# 4d_-_BSPD_Detection_Timer.net
KiCad netlist of a schematic drawn in Altium Designer
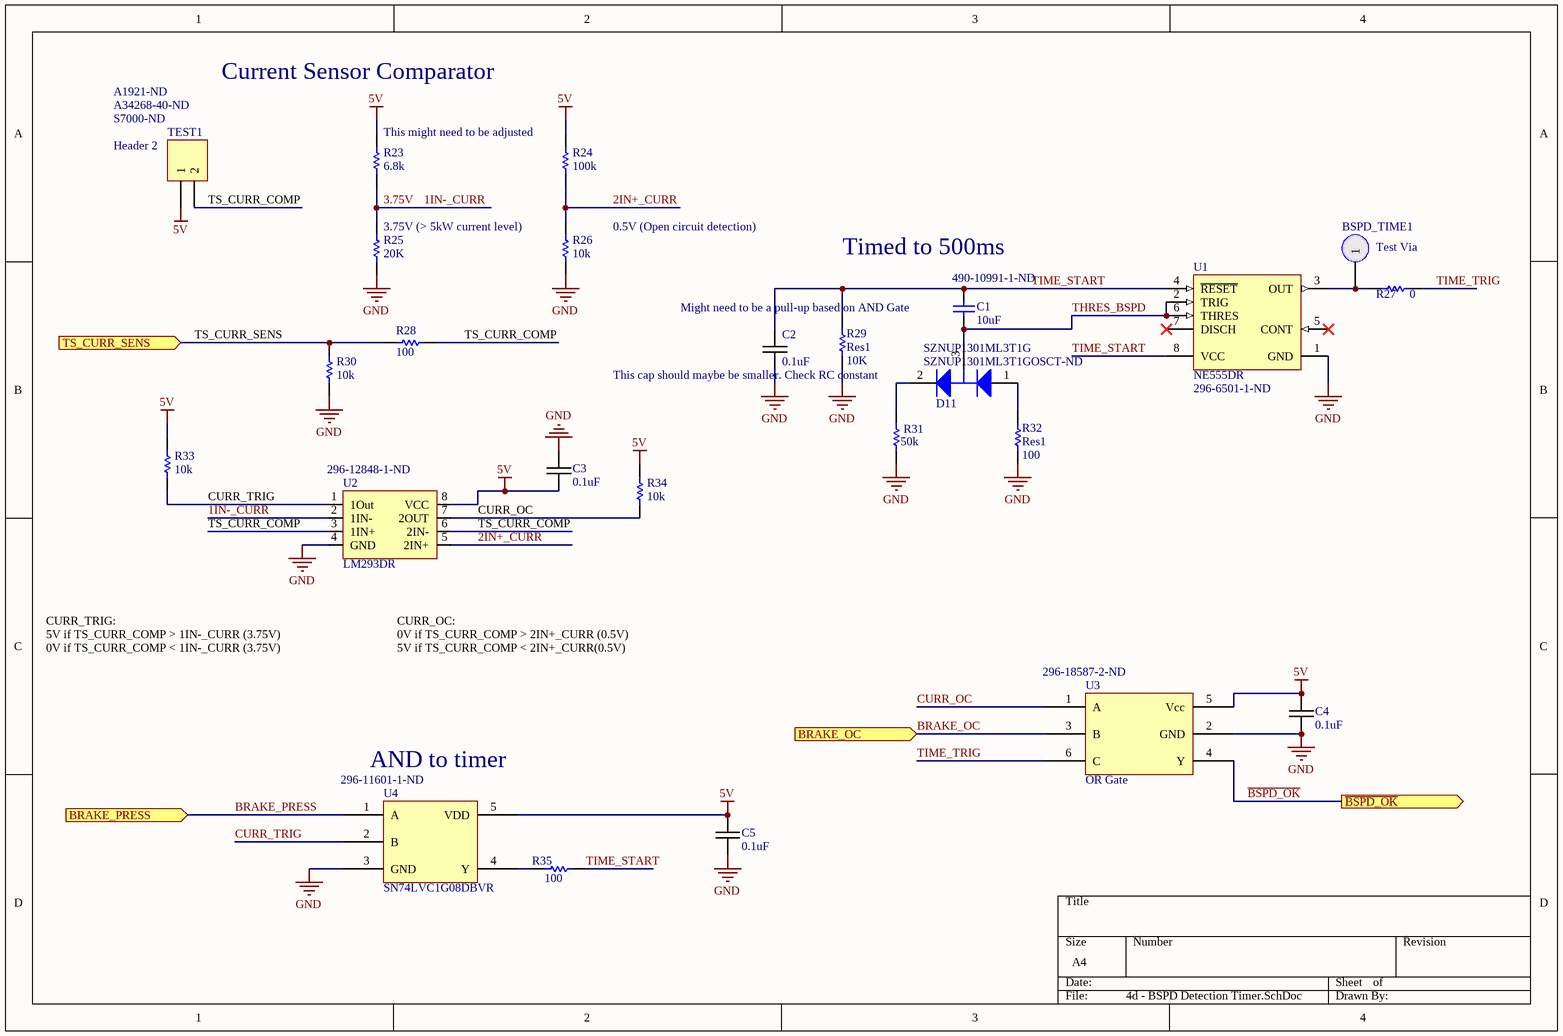
[diagram p0: 4d - BSPD Detection Timer.SchDoc]

(export (version "E")
  (design (tool "Eeschema 10.0.6"))
  (components
    (comp (ref "BSPD_TIME1")
      (value "Test Via")
      (footprint "Test Via")
      (libsource (lib "BRAKETEMPComponents") (part "Test VIa"))
    )
    (comp (ref "C1")
      (value "10uF")
      (footprint "1608[0603]")
      (description "Capacitor (Semiconductor SIM Model)")
      (fields
        (field (name "SUPPLIER PART NUMBER 1") "490-10991-1-ND")
        (field (name "Comment") "Cap Semi")
        (field (name "PUBLISHER") "Altium Limited")
      )
      (libsource (lib "Miscellaneous Devices") (part "Cap Semi"))
    )
    (comp (ref "C2")
      (value "0.1uF")
      (footprint "1608[0603]")
      (description "CAP CER 0.1UF 50V X7R 0603")
      (fields
        (field (name "MANUFACTURER") "Kemet")
        (field (name "MANUFACTURER PART NUMBER") "C0603C104K5RACAUTO")
      )
      (libsource (lib "vh_altium_library") (part "0805C-100nF-25V-X7R-MUR"))
    )
    (comp (ref "C3")
      (value "0.1uF")
      (footprint "1608[0603]")
      (description "CAP CER 0.1UF 50V X7R 0603")
      (fields
        (field (name "MANUFACTURER") "Kemet")
        (field (name "MANUFACTURER PART NUMBER") "C0603C104K5RACAUTO")
      )
      (libsource (lib "vh_altium_library") (part "0805C-100nF-25V-X7R-MUR"))
    )
    (comp (ref "C4")
      (value "0.1uF")
      (footprint "1608[0603]")
      (description "CAP CER 0.1UF 50V X7R 0603")
      (fields
        (field (name "MANUFACTURER") "Kemet")
        (field (name "MANUFACTURER PART NUMBER") "C0603C104K5RACAUTO")
      )
      (libsource (lib "vh_altium_library") (part "0805C-100nF-25V-X7R-MUR"))
    )
    (comp (ref "C5")
      (value "0.1uF")
      (footprint "1608[0603]")
      (description "CAP CER 0.1UF 50V X7R 0603")
      (fields
        (field (name "MANUFACTURER") "Kemet")
        (field (name "MANUFACTURER PART NUMBER") "C0603C104K5RACAUTO")
      )
      (libsource (lib "vh_altium_library") (part "0805C-100nF-25V-X7R-MUR"))
    )
    (comp (ref "D11")
      (value "SZNUP1301ML3T1G")
      (footprint "ONSC-SOT-23-3-318-08_V")
      (fields
        (field (name "MANUFACTURER") "On Semiconductor")
        (field (name "SUPPLIER PART NUMBER 1") "SZNUP1301ML3T1GOSCT-ND")
      )
      (libsource (lib "Altium Content Vault") (part "ONSC-NUP1301-SOT-23-3-318-08"))
    )
    (comp (ref "R23")
      (value "Volt. Div. R1")
      (footprint "1608[0603]")
      (description "RES SMD 6.8K OHM 5% 1/4W 0603")
      (fields
        (field (name "MANUFACTURER") "Rohm Semiconductor")
        (field (name "MANUFACTURER PART NUMBER") "ESR03EZPJ682")
        (field (name "RESISTANCE (OHMS)") "6.8k")
      )
      (libsource (lib "Miscellaneous Devices") (part "Res1"))
    )
    (comp (ref "R24")
      (value "Volt. Div. R1")
      (footprint "1608[0603]")
      (description "RES SMD 6.8K OHM 5% 1/4W 0603")
      (fields
        (field (name "MANUFACTURER") "Rohm Semiconductor")
        (field (name "MANUFACTURER PART NUMBER") "ESR03EZPJ682")
        (field (name "RESISTANCE (OHMS)") "100k")
      )
      (libsource (lib "Miscellaneous Devices") (part "Res1"))
    )
    (comp (ref "R25")
      (value "20K")
      (footprint "1608[0603]")
      (description "RES SMD 20K OHM 5% 1/4W 0603")
      (fields
        (field (name "MANUFACTURER") "Rohm Semiconductor")
        (field (name "MANUFACTURER PART NUMBER") "ESR03EZPJ203")
        (field (name "PUBLISHER") "Altium Limited")
      )
      (libsource (lib "Miscellaneous Devices") (part "Res1"))
    )
    (comp (ref "R26")
      (value "10k")
      (footprint "1608[0603]")
      (description "RES SMD 20K OHM 5% 1/4W 0603")
      (fields
        (field (name "MANUFACTURER") "Rohm Semiconductor")
        (field (name "MANUFACTURER PART NUMBER") "ESR03EZPJ203")
        (field (name "PUBLISHER") "Altium Limited")
      )
      (libsource (lib "Miscellaneous Devices") (part "Res1"))
    )
    (comp (ref "R27")
      (value "0")
      (footprint "1608[0603]")
      (description "RES SMD 0.0 OHM JUMPER 1/4W 0603")
      (fields
        (field (name "MANUFACTURER") "Vishay Dale")
        (field (name "MANUFACTURER PART NUMBER") "CRCW06030000Z0EAHP")
        (field (name "PUBLISHER") "Altium Limited")
      )
      (libsource (lib "Miscellaneous Devices") (part "Res1"))
    )
    (comp (ref "R28")
      (value "100")
      (footprint "1608[0603]")
      (description "RES SMD 20K OHM 5% 1/4W 0603")
      (fields
        (field (name "MANUFACTURER") "Rohm Semiconductor")
        (field (name "MANUFACTURER PART NUMBER") "ESR03EZPJ203")
        (field (name "PUBLISHER") "Altium Limited")
      )
      (libsource (lib "Miscellaneous Devices") (part "Res1"))
    )
    (comp (ref "R29")
      (value "Res1")
      (footprint "1608[0603]")
      (description "RES SMD 10K OHM 5% 1/4W 0603")
      (fields
        (field (name "ALTIUM_VALUE") "10K")
        (field (name "MANUFACTURER") "Rohm Semiconductor")
        (field (name "MANUFACTURER PART NUMBER") "ESR03EZPJ103")
        (field (name "PUBLISHER") "Altium Limited")
      )
      (libsource (lib "Miscellaneous Devices") (part "Res1"))
    )
    (comp (ref "R30")
      (value "10k")
      (footprint "1608[0603]")
      (description "RES SMD 20K OHM 5% 1/4W 0603")
      (fields
        (field (name "MANUFACTURER") "Rohm Semiconductor")
        (field (name "MANUFACTURER PART NUMBER") "ESR03EZPJ203")
        (field (name "PUBLISHER") "Altium Limited")
      )
      (libsource (lib "Miscellaneous Devices") (part "Res1"))
    )
    (comp (ref "R31")
      (value "50k")
      (footprint "RESC0603(1608)_L")
      (description "0603 (1608 Metric) Chip Resistor")
      (libsource (lib "Altium Content Vault") (part "RES_3"))
    )
    (comp (ref "R32")
      (value "Res1")
      (footprint "1608[0603]")
      (description "RES SMD 10K OHM 5% 1/4W 0603")
      (fields
        (field (name "ALTIUM_VALUE") "100")
        (field (name "MANUFACTURER") "Rohm Semiconductor")
        (field (name "MANUFACTURER PART NUMBER") "ESR03EZPJ103")
        (field (name "PUBLISHER") "Altium Limited")
      )
      (libsource (lib "Miscellaneous Devices") (part "Res1"))
    )
    (comp (ref "R33")
      (value "10k")
      (footprint "1608[0603]")
      (description "RES SMD 20K OHM 5% 1/4W 0603")
      (fields
        (field (name "MANUFACTURER") "Rohm Semiconductor")
        (field (name "MANUFACTURER PART NUMBER") "ESR03EZPJ203")
        (field (name "PUBLISHER") "Altium Limited")
      )
      (libsource (lib "Miscellaneous Devices") (part "Res1"))
    )
    (comp (ref "R34")
      (value "10k")
      (footprint "1608[0603]")
      (description "RES SMD 20K OHM 5% 1/4W 0603")
      (fields
        (field (name "MANUFACTURER") "Rohm Semiconductor")
        (field (name "MANUFACTURER PART NUMBER") "ESR03EZPJ203")
        (field (name "PUBLISHER") "Altium Limited")
      )
      (libsource (lib "Miscellaneous Devices") (part "Res1"))
    )
    (comp (ref "R35")
      (value "100")
      (footprint "1608[0603]")
      (description "RES SMD 20K OHM 5% 1/4W 0603")
      (fields
        (field (name "MANUFACTURER") "Rohm Semiconductor")
        (field (name "MANUFACTURER PART NUMBER") "ESR03EZPJ203")
        (field (name "PUBLISHER") "Altium Limited")
      )
      (libsource (lib "Miscellaneous Devices") (part "Res1"))
    )
    (comp (ref "TEST1")
      (value "Header 2")
      (footprint "2 Pin Connector")
      (description "Header, 2-Pin")
      (fields
        (field (name "MANUFACTURER") "Harwin Inc.")
        (field (name "MANUFACTURER PART NUMBER") "M20-9990246")
        (field (name "SUPPLIER PART NUMBER 1") "S7000-ND")
        (field (name "SUPPLIER PART NUMBER 2") "A34268-40-ND")
        (field (name "SUPPLIER PART NUMBER 3") "A1921-ND")
        (field (name "PUBLISHER") "Altium Limited")
      )
      (libsource (lib "Miscellaneous Connectors") (part "Header 2"))
    )
    (comp (ref "U1")
      (value "NE555DR")
      (footprint "D0008A_M")
      (fields (field (name "SUPPLIER PART NUMBER 1") "296-6501-1-ND"))
      (libsource (lib "Altium Content Vault") (part "CMP-1685-00007-1"))
    )
    (comp (ref "U2")
      (value "LM293DR")
      (footprint "LM293DR")
      (description "IC Dual Comparator")
      (fields (field (name "SUPPLIER PART NUMBER 1") "296-12848-1-ND"))
      (libsource (lib "ACB_lib") (part "LM293DR"))
    )
    (comp (ref "U3")
      (value "OR Gate")
      (footprint "SOT23-6_M")
      (fields (field (name "SUPPLIER PART NUMBER 1") "296-18587-2-ND"))
      (libsource (lib "Schlib1") (part "4-input OR Gate"))
    )
    (comp (ref "U4")
      (value "SN74LVC1G08DBVR")
      (footprint "SSOP5-P-0.95")
      (fields (field (name "SUPPLIER PART NUMBER 1") "296-11601-1-ND"))
      (libsource (lib "ACB_lib") (part "SN74LVC1G08DBVR"))
    )
  )
  (nets
    (net (code "1") (name "/1IN-_CURR") (class "Default")
      (node (ref "R23") (pin "1") (pinfunction "1_1") (pintype "passive"))
      (node (ref "R25") (pin "2") (pinfunction "2_2") (pintype "passive"))
      (node (ref "U2") (pin "2") (pinfunction "1IN-_2") (pintype "passive"))
    )
    (net (code "2") (name "/2IN+_CURR") (class "Default")
      (node (ref "R24") (pin "1") (pinfunction "1_1") (pintype "passive"))
      (node (ref "R26") (pin "2") (pinfunction "2_2") (pintype "passive"))
      (node (ref "U2") (pin "5") (pinfunction "2IN+_5") (pintype "passive"))
    )
    (net (code "3") (name "/BRAKE_OC") (class "Default")
      (node (ref "U3") (pin "3") (pinfunction "B_3") (pintype "passive"))
    )
    (net (code "4") (name "/BRAKE_PRESS") (class "Default")
      (node (ref "U4") (pin "1") (pinfunction "A_1") (pintype "passive"))
    )
    (net (code "5") (name "/CURR_OC") (class "Default")
      (node (ref "R34") (pin "1") (pinfunction "1_1") (pintype "passive"))
      (node (ref "U2") (pin "7") (pinfunction "2OUT_7") (pintype "passive"))
      (node (ref "U3") (pin "1") (pinfunction "A_1") (pintype "passive"))
    )
    (net (code "6") (name "/CURR_TRIG") (class "Default")
      (node (ref "R33") (pin "1") (pinfunction "1_1") (pintype "passive"))
      (node (ref "U2") (pin "1") (pinfunction "1Out_1") (pintype "passive"))
      (node (ref "U4") (pin "2") (pinfunction "B_2") (pintype "passive"))
    )
    (net (code "7") (name "/THRES_BSPD") (class "Default")
      (node (ref "C1") (pin "1") (pinfunction "1_1") (pintype "passive"))
      (node (ref "D11") (pin "3") (pinfunction "K/A_3") (pintype "passive"))
      (node (ref "U1") (pin "2") (pinfunction "TRIG_2") (pintype "input"))
      (node (ref "U1") (pin "6") (pinfunction "THRES_6") (pintype "input"))
    )
    (net (code "8") (name "/TIME_START") (class "Default")
      (node (ref "C1") (pin "2") (pinfunction "2_2") (pintype "passive"))
      (node (ref "C2") (pin "1") (pintype "passive"))
      (node (ref "R29") (pin "2") (pinfunction "2_2") (pintype "passive"))
      (node (ref "R35") (pin "1") (pinfunction "1_1") (pintype "passive"))
      (node (ref "U1") (pin "4") (pinfunction "~{RESET}_4") (pintype "input"))
      (node (ref "U1") (pin "8") (pinfunction "VCC_8") (pintype "power_in"))
    )
    (net (code "9") (name "/TIME_TRIG") (class "Default")
      (node (ref "R27") (pin "1") (pinfunction "1_1") (pintype "passive"))
      (node (ref "U3") (pin "6") (pinfunction "C_6") (pintype "passive"))
    )
    (net (code "10") (name "/TS_CURR_COMP") (class "Default")
      (node (ref "R28") (pin "1") (pinfunction "1_1") (pintype "passive"))
      (node (ref "TEST1") (pin "2") (pinfunction "2_2") (pintype "passive"))
      (node (ref "U2") (pin "3") (pinfunction "1IN+_3") (pintype "passive"))
      (node (ref "U2") (pin "6") (pinfunction "2IN-_6") (pintype "passive"))
    )
    (net (code "11") (name "/TS_CURR_SENS") (class "Default")
      (node (ref "R28") (pin "2") (pinfunction "2_2") (pintype "passive"))
      (node (ref "R30") (pin "2") (pinfunction "2_2") (pintype "passive"))
    )
    (net (code "12") (name "/~{BSPD_OK}") (class "Default")
      (node (ref "U3") (pin "4") (pinfunction "Y_4") (pintype "passive"))
    )
    (net (code "13") (name "5V") (class "Default")
      (node (ref "C3") (pin "1") (pintype "passive"))
      (node (ref "C4") (pin "1") (pintype "passive"))
      (node (ref "C5") (pin "1") (pintype "passive"))
      (node (ref "R23") (pin "2") (pinfunction "2_2") (pintype "passive"))
      (node (ref "R24") (pin "2") (pinfunction "2_2") (pintype "passive"))
      (node (ref "R33") (pin "2") (pinfunction "2_2") (pintype "passive"))
      (node (ref "R34") (pin "2") (pinfunction "2_2") (pintype "passive"))
      (node (ref "TEST1") (pin "1") (pinfunction "1_1") (pintype "passive"))
      (node (ref "U2") (pin "8") (pinfunction "VCC_8") (pintype "passive"))
      (node (ref "U3") (pin "5") (pinfunction "Vcc_5") (pintype "passive"))
      (node (ref "U4") (pin "5") (pinfunction "VDD_5") (pintype "passive"))
    )
    (net (code "14") (name "GND") (class "Default")
      (node (ref "C2") (pin "2") (pintype "passive"))
      (node (ref "C3") (pin "2") (pintype "passive"))
      (node (ref "C4") (pin "2") (pintype "passive"))
      (node (ref "C5") (pin "2") (pintype "passive"))
      (node (ref "R25") (pin "1") (pinfunction "1_1") (pintype "passive"))
      (node (ref "R26") (pin "1") (pinfunction "1_1") (pintype "passive"))
      (node (ref "R29") (pin "1") (pinfunction "1_1") (pintype "passive"))
      (node (ref "R30") (pin "1") (pinfunction "1_1") (pintype "passive"))
      (node (ref "R31") (pin "1") (pinfunction "1_1") (pintype "passive"))
      (node (ref "R32") (pin "1") (pinfunction "1_1") (pintype "passive"))
      (node (ref "U1") (pin "1") (pinfunction "GND_1") (pintype "power_in"))
      (node (ref "U2") (pin "4") (pinfunction "GND_4") (pintype "passive"))
      (node (ref "U3") (pin "2") (pinfunction "GND_2") (pintype "passive"))
      (node (ref "U4") (pin "3") (pinfunction "GND_3") (pintype "passive"))
    )
    (net (code "15") (name "Net-(D11-A)") (class "Default")
      (node (ref "D11") (pin "1") (pinfunction "A_1") (pintype "passive"))
      (node (ref "R32") (pin "2") (pinfunction "2_2") (pintype "passive"))
    )
    (net (code "16") (name "Net-(D11-K)") (class "Default")
      (node (ref "D11") (pin "2") (pinfunction "K_2") (pintype "passive"))
      (node (ref "R31") (pin "2") (pinfunction "2_2") (pintype "passive"))
    )
    (net (code "17") (name "Net-(U1-OUT)") (class "Default")
      (node (ref "BSPD_TIME1") (pin "1") (pinfunction "1_1") (pintype "passive"))
      (node (ref "R27") (pin "2") (pinfunction "2_2") (pintype "passive"))
      (node (ref "U1") (pin "3") (pinfunction "OUT_3") (pintype "output"))
    )
    (net (code "18") (name "Net-(U4-Y)") (class "Default")
      (node (ref "R35") (pin "2") (pinfunction "2_2") (pintype "passive"))
      (node (ref "U4") (pin "4") (pinfunction "Y_4") (pintype "passive"))
    )
    (net (code "19") (name "unconnected-(U1-CONT-Pad5)") (class "Default")
      (node (ref "U1") (pin "5") (pinfunction "CONT_5") (pintype "input+no_connect"))
    )
    (net (code "20") (name "unconnected-(U1-DISCH-Pad7)") (class "Default")
      (node (ref "U1") (pin "7") (pinfunction "DISCH_7") (pintype "open_collector+no_connect"))
    )
  )
)
